# mrShark_05_a.net
KiCad netlist of a schematic drawn in EAGLE
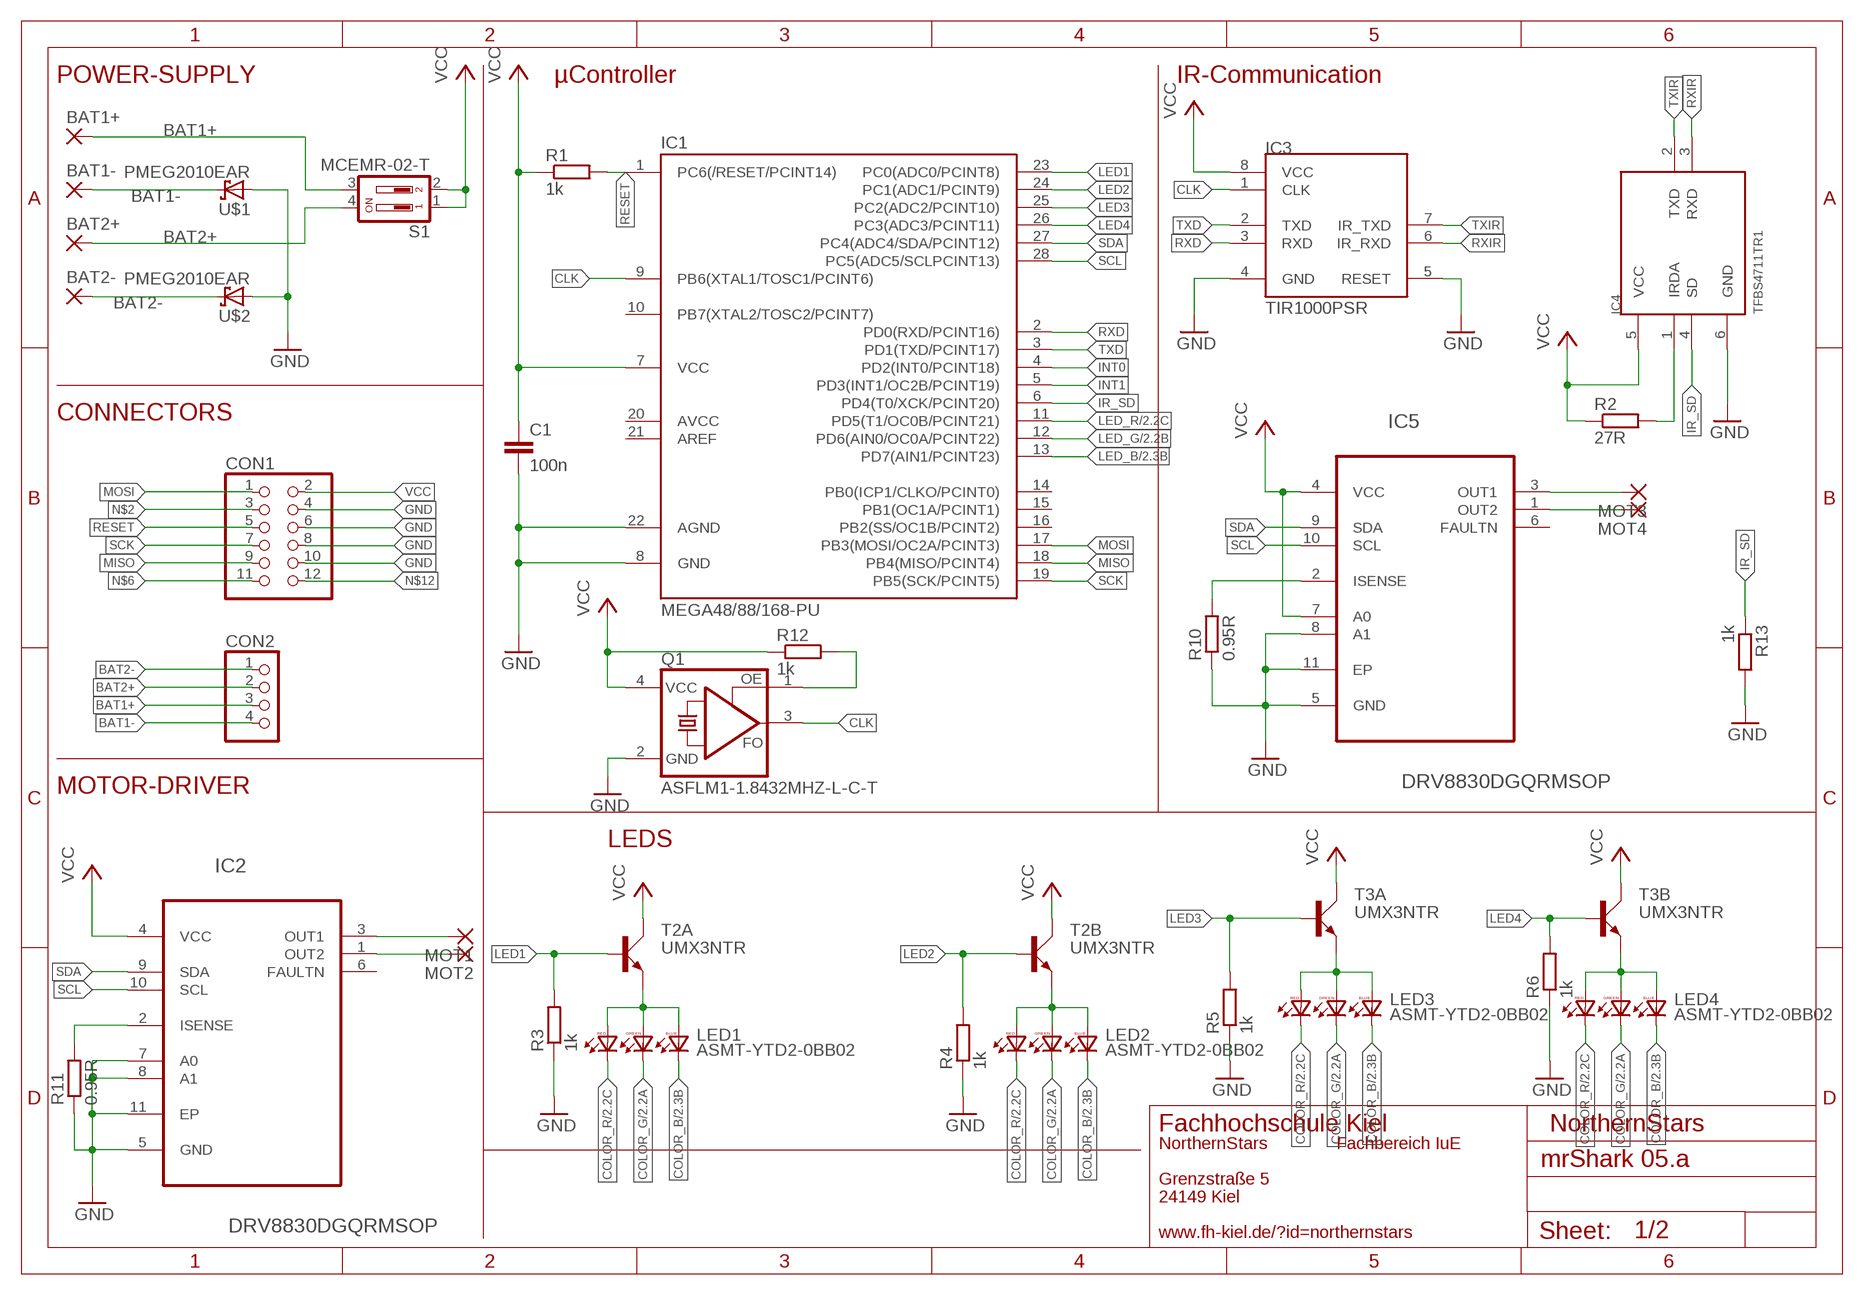
[diagram p0: schematic, sheet 1]
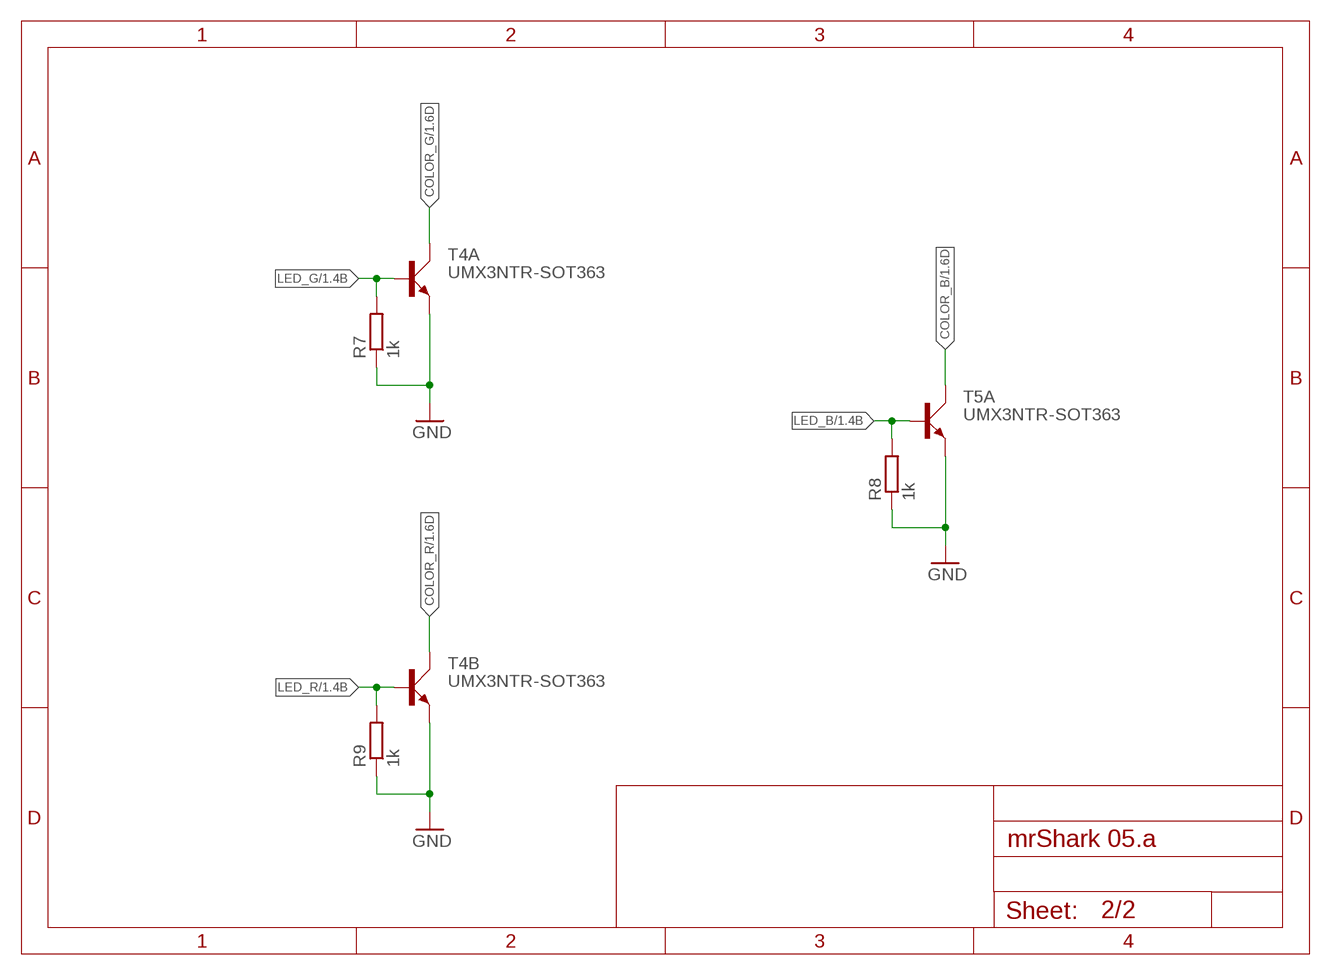
[diagram p1: schematic, sheet 2]

(export (version "E")
  (design (tool "Eeschema 10.0.6"))
  (components
    (comp (ref "R7")
      (value "1k")
      (footprint "eagle-import:R1206")
      (libsource (lib "eagle-import") (part "R-EU_R1206"))
    )
    (comp (ref "R8")
      (value "1k")
      (footprint "eagle-import:R1206")
      (libsource (lib "eagle-import") (part "R-EU_R1206"))
    )
    (comp (ref "R9")
      (value "1k")
      (footprint "eagle-import:R1206")
      (libsource (lib "eagle-import") (part "R-EU_R1206"))
    )
    (comp (ref "T4")
      (value "UMX3NTR-SOT363")
      (footprint "eagle-import:SOT363_INFINEON")
      (libsource (lib "eagle-import") (part "UMX3NTR-SOT363"))
    )
    (comp (ref "T5")
      (value "UMX3NTR-SOT363")
      (footprint "eagle-import:SOT363_INFINEON")
      (libsource (lib "eagle-import") (part "UMX3NTR-SOT363"))
    )
    (comp (ref "BAT1+")
      (value "1,6/0,9")
      (footprint "eagle-import:1,6_0,9")
      (libsource (lib "eagle-import") (part "1,6/0,9"))
    )
    (comp (ref "BAT1-")
      (value "1,6/0,9")
      (footprint "eagle-import:1,6_0,9")
      (libsource (lib "eagle-import") (part "1,6/0,9"))
    )
    (comp (ref "BAT2+")
      (value "1,6/0,9")
      (footprint "eagle-import:1,6_0,9")
      (libsource (lib "eagle-import") (part "1,6/0,9"))
    )
    (comp (ref "BAT2-")
      (value "1,6/0,9")
      (footprint "eagle-import:1,6_0,9")
      (libsource (lib "eagle-import") (part "1,6/0,9"))
    )
    (comp (ref "C1")
      (value "100n")
      (footprint "eagle-import:C1206")
      (libsource (lib "eagle-import") (part "C-EUC1206"))
    )
    (comp (ref "CON1")
      (value "PINHD-2X06_2.54-SMD")
      (footprint "eagle-import:2X06SMD")
      (libsource (lib "eagle-import") (part "PINHD-2X06_2.54-SMD"))
    )
    (comp (ref "CON2")
      (value "PINHD-1X04_2.54-SMD-90°")
      (footprint "eagle-import:1X04SMD_90")
      (libsource (lib "eagle-import") (part "PINHD-1X04_2.54-SMD-90°"))
    )
    (comp (ref "IC1")
      (value "MEGA48/88/168-PU")
      (footprint "eagle-import:DIL28-3")
      (libsource (lib "eagle-import") (part "MEGA48/88/168-PU"))
    )
    (comp (ref "IC2")
      (value "DRV8830DGQRMSOP")
      (footprint "eagle-import:SOP65P640X110-15N")
      (fields (field (name "MPN") "DRV8830DGQR"))
      (libsource (lib "eagle-import") (part "DRV8830DGQRMSOP"))
    )
    (comp (ref "IC3")
      (value "TIR1000PSR")
      (footprint "eagle-import:SO-08")
      (libsource (lib "eagle-import") (part "TIR1000PSR"))
    )
    (comp (ref "IC4")
      (value "TFBS4711TR1")
      (footprint "eagle-import:TFBS4711")
      (libsource (lib "eagle-import") (part "TFBS4711TR1"))
    )
    (comp (ref "IC5")
      (value "DRV8830DGQRMSOP")
      (footprint "eagle-import:SOP65P640X110-15N")
      (fields (field (name "MPN") "DRV8830DGQR"))
      (libsource (lib "eagle-import") (part "DRV8830DGQRMSOP"))
    )
    (comp (ref "LED1")
      (value "ASMT-YTD2-0BB02")
      (footprint "eagle-import:PLCC6")
      (libsource (lib "eagle-import") (part "PLCC6"))
    )
    (comp (ref "LED2")
      (value "ASMT-YTD2-0BB02")
      (footprint "eagle-import:PLCC6")
      (libsource (lib "eagle-import") (part "PLCC6"))
    )
    (comp (ref "LED3")
      (value "ASMT-YTD2-0BB02")
      (footprint "eagle-import:PLCC6")
      (libsource (lib "eagle-import") (part "PLCC6"))
    )
    (comp (ref "LED4")
      (value "ASMT-YTD2-0BB02")
      (footprint "eagle-import:PLCC6")
      (libsource (lib "eagle-import") (part "PLCC6"))
    )
    (comp (ref "MOT1")
      (value "1,6/0,9")
      (footprint "eagle-import:1,6_0,9")
      (libsource (lib "eagle-import") (part "1,6/0,9"))
    )
    (comp (ref "MOT2")
      (value "1,6/0,9")
      (footprint "eagle-import:1,6_0,9")
      (libsource (lib "eagle-import") (part "1,6/0,9"))
    )
    (comp (ref "MOT3")
      (value "1,6/0,9")
      (footprint "eagle-import:1,6_0,9")
      (libsource (lib "eagle-import") (part "1,6/0,9"))
    )
    (comp (ref "MOT4")
      (value "1,6/0,9")
      (footprint "eagle-import:1,6_0,9")
      (libsource (lib "eagle-import") (part "1,6/0,9"))
    )
    (comp (ref "Q1")
      (value "ASFLM1-1.8432MHZ-L-C-T")
      (footprint "eagle-import:HC536")
      (libsource (lib "eagle-import") (part "HC536R"))
    )
    (comp (ref "R1")
      (value "1k")
      (footprint "eagle-import:R1206")
      (libsource (lib "eagle-import") (part "R-EU_R1206"))
    )
    (comp (ref "R2")
      (value "27R")
      (footprint "eagle-import:R1206")
      (libsource (lib "eagle-import") (part "R-EU_R1206"))
    )
    (comp (ref "R3")
      (value "1k")
      (footprint "eagle-import:R1206")
      (libsource (lib "eagle-import") (part "R-EU_R1206"))
    )
    (comp (ref "R4")
      (value "1k")
      (footprint "eagle-import:R1206")
      (libsource (lib "eagle-import") (part "R-EU_R1206"))
    )
    (comp (ref "R5")
      (value "1k")
      (footprint "eagle-import:R1206")
      (libsource (lib "eagle-import") (part "R-EU_R1206"))
    )
    (comp (ref "R6")
      (value "1k")
      (footprint "eagle-import:R1206")
      (libsource (lib "eagle-import") (part "R-EU_R1206"))
    )
    (comp (ref "R10")
      (value "0.95R")
      (footprint "eagle-import:R1206")
      (libsource (lib "eagle-import") (part "R-EU_R1206"))
    )
    (comp (ref "R11")
      (value "0.95R")
      (footprint "eagle-import:R1206")
      (libsource (lib "eagle-import") (part "R-EU_R1206"))
    )
    (comp (ref "R12")
      (value "1k")
      (footprint "eagle-import:R1206")
      (libsource (lib "eagle-import") (part "R-EU_R1206"))
    )
    (comp (ref "R13")
      (value "1k")
      (footprint "eagle-import:R1206")
      (libsource (lib "eagle-import") (part "R-EU_R1206"))
    )
    (comp (ref "S1")
      (value "MCEMR-02-T")
      (footprint "eagle-import:CTS-219-02")
      (libsource (lib "eagle-import") (part "219-02"))
    )
    (comp (ref "T2")
      (value "UMX3NTR")
      (footprint "eagle-import:SOT363_INFINEON")
      (libsource (lib "eagle-import") (part "UMX3NTR-SOT363"))
    )
    (comp (ref "T3")
      (value "UMX3NTR")
      (footprint "eagle-import:SOT363_INFINEON")
      (libsource (lib "eagle-import") (part "UMX3NTR-SOT363"))
    )
    (comp (ref "U$1")
      (value "PMEG2010EAR")
      (footprint "eagle-import:SOD323-R")
      (libsource (lib "eagle-import") (part "PMEG2010EAR"))
    )
    (comp (ref "U$2")
      (value "PMEG2010EAR")
      (footprint "eagle-import:SOD323-R")
      (libsource (lib "eagle-import") (part "PMEG2010EAR"))
    )
  )
  (nets
    (net (code "1") (name "BAT1+") (class "Default")
      (node (ref "BAT1+") (pin "1") (pinfunction "P_1") (pintype "passive"))
      (node (ref "CON2") (pin "3") (pinfunction "3_3") (pintype "passive"))
      (node (ref "S1") (pin "3") (pinfunction "3_3") (pintype "passive"))
    )
    (net (code "2") (name "BAT1-") (class "Default")
      (node (ref "BAT1-") (pin "1") (pinfunction "P_1") (pintype "passive"))
      (node (ref "CON2") (pin "4") (pinfunction "4_4") (pintype "passive"))
      (node (ref "U$1") (pin "C") (pinfunction "C_C") (pintype "passive"))
    )
    (net (code "3") (name "BAT2+") (class "Default")
      (node (ref "BAT2+") (pin "1") (pinfunction "P_1") (pintype "passive"))
      (node (ref "CON2") (pin "2") (pinfunction "2_2") (pintype "passive"))
      (node (ref "S1") (pin "4") (pinfunction "4_4") (pintype "passive"))
    )
    (net (code "4") (name "BAT2-") (class "Default")
      (node (ref "BAT2-") (pin "1") (pinfunction "P_1") (pintype "passive"))
      (node (ref "CON2") (pin "1") (pinfunction "1_1") (pintype "passive"))
      (node (ref "U$2") (pin "C") (pinfunction "C_C") (pintype "passive"))
    )
    (net (code "5") (name "CLK") (class "Default")
      (node (ref "IC1") (pin "9") (pinfunction "PB6(XTAL1/TOSC1/PCINT6)_9") (pintype "bidirectional"))
      (node (ref "IC3") (pin "1") (pinfunction "CLK_1") (pintype "bidirectional"))
      (node (ref "Q1") (pin "3") (pinfunction "FO_3") (pintype "output"))
    )
    (net (code "6") (name "COLOR_B") (class "Default")
      (node (ref "LED1") (pin "1") (pinfunction "BC_1") (pintype "passive"))
      (node (ref "LED2") (pin "1") (pinfunction "BC_1") (pintype "passive"))
      (node (ref "LED3") (pin "1") (pinfunction "BC_1") (pintype "passive"))
      (node (ref "LED4") (pin "1") (pinfunction "BC_1") (pintype "passive"))
      (node (ref "T5") (pin "6") (pinfunction "C_6") (pintype "passive"))
    )
    (net (code "7") (name "COLOR_G") (class "Default")
      (node (ref "LED1") (pin "2") (pinfunction "GC_2") (pintype "passive"))
      (node (ref "LED2") (pin "2") (pinfunction "GC_2") (pintype "passive"))
      (node (ref "LED3") (pin "2") (pinfunction "GC_2") (pintype "passive"))
      (node (ref "LED4") (pin "2") (pinfunction "GC_2") (pintype "passive"))
      (node (ref "T4") (pin "6") (pinfunction "C_6") (pintype "passive"))
    )
    (net (code "8") (name "COLOR_R") (class "Default")
      (node (ref "LED1") (pin "3") (pinfunction "RC_3") (pintype "passive"))
      (node (ref "LED2") (pin "3") (pinfunction "RC_3") (pintype "passive"))
      (node (ref "LED3") (pin "3") (pinfunction "RC_3") (pintype "passive"))
      (node (ref "LED4") (pin "3") (pinfunction "RC_3") (pintype "passive"))
      (node (ref "T4") (pin "4") (pinfunction "C_4") (pintype "passive"))
    )
    (net (code "9") (name "GND") (class "Default")
      (node (ref "C1") (pin "2") (pinfunction "2_2") (pintype "passive"))
      (node (ref "CON1") (pin "10") (pinfunction "10_10") (pintype "passive"))
      (node (ref "CON1") (pin "4") (pinfunction "4_4") (pintype "passive"))
      (node (ref "CON1") (pin "6") (pinfunction "6_6") (pintype "passive"))
      (node (ref "CON1") (pin "8") (pinfunction "8_8") (pintype "passive"))
      (node (ref "IC1") (pin "22") (pinfunction "AGND_22") (pintype "power_in"))
      (node (ref "IC1") (pin "8") (pinfunction "GND_8") (pintype "power_in"))
      (node (ref "IC2") (pin "11") (pinfunction "EP_11") (pintype "passive"))
      (node (ref "IC2") (pin "5") (pinfunction "GND_5") (pintype "passive"))
      (node (ref "IC2") (pin "7") (pinfunction "A0_7") (pintype "input"))
      (node (ref "IC2") (pin "8") (pinfunction "A1_8") (pintype "input"))
      (node (ref "IC3") (pin "4") (pinfunction "GND_4") (pintype "bidirectional"))
      (node (ref "IC3") (pin "5") (pinfunction "RESET_5") (pintype "bidirectional"))
      (node (ref "IC4") (pin "6") (pinfunction "GND_6") (pintype "bidirectional"))
      (node (ref "IC5") (pin "11") (pinfunction "EP_11") (pintype "passive"))
      (node (ref "IC5") (pin "5") (pinfunction "GND_5") (pintype "passive"))
      (node (ref "IC5") (pin "8") (pinfunction "A1_8") (pintype "input"))
      (node (ref "Q1") (pin "2") (pinfunction "GND_2") (pintype "power_in"))
      (node (ref "R10") (pin "1") (pinfunction "1_1") (pintype "passive"))
      (node (ref "R11") (pin "1") (pinfunction "1_1") (pintype "passive"))
      (node (ref "R13") (pin "2") (pinfunction "2_2") (pintype "passive"))
      (node (ref "R3") (pin "1") (pinfunction "1_1") (pintype "passive"))
      (node (ref "R4") (pin "1") (pinfunction "1_1") (pintype "passive"))
      (node (ref "R5") (pin "1") (pinfunction "1_1") (pintype "passive"))
      (node (ref "R6") (pin "1") (pinfunction "1_1") (pintype "passive"))
      (node (ref "R7") (pin "1") (pinfunction "1_1") (pintype "passive"))
      (node (ref "R8") (pin "1") (pinfunction "1_1") (pintype "passive"))
      (node (ref "R9") (pin "1") (pinfunction "1_1") (pintype "passive"))
      (node (ref "T4") (pin "1") (pinfunction "E_1") (pintype "passive"))
      (node (ref "T4") (pin "5") (pinfunction "E_5") (pintype "passive"))
      (node (ref "T5") (pin "1") (pinfunction "E_1") (pintype "passive"))
      (node (ref "U$1") (pin "A") (pinfunction "A_A") (pintype "passive"))
      (node (ref "U$2") (pin "A") (pinfunction "A_A") (pintype "passive"))
    )
    (net (code "10") (name "INT0") (class "Default")
      (node (ref "IC1") (pin "4") (pinfunction "PD2(INT0/PCINT18)_4") (pintype "bidirectional"))
    )
    (net (code "11") (name "INT1") (class "Default")
      (node (ref "IC1") (pin "5") (pinfunction "PD3(INT1/OC2B/PCINT19)_5") (pintype "bidirectional"))
    )
    (net (code "12") (name "IR_SD") (class "Default")
      (node (ref "IC1") (pin "6") (pinfunction "PD4(T0/XCK/PCINT20)_6") (pintype "bidirectional"))
      (node (ref "IC4") (pin "4") (pinfunction "SD_4") (pintype "bidirectional"))
      (node (ref "R13") (pin "1") (pinfunction "1_1") (pintype "passive"))
    )
    (net (code "13") (name "LED1") (class "Default")
      (node (ref "IC1") (pin "23") (pinfunction "PC0(ADC0/PCINT8)_23") (pintype "bidirectional"))
      (node (ref "R3") (pin "2") (pinfunction "2_2") (pintype "passive"))
      (node (ref "T2") (pin "2") (pinfunction "B_2") (pintype "passive"))
    )
    (net (code "14") (name "LED2") (class "Default")
      (node (ref "IC1") (pin "24") (pinfunction "PC1(ADC1/PCINT9)_24") (pintype "bidirectional"))
      (node (ref "R4") (pin "2") (pinfunction "2_2") (pintype "passive"))
      (node (ref "T2") (pin "3") (pinfunction "B_3") (pintype "passive"))
    )
    (net (code "15") (name "LED3") (class "Default")
      (node (ref "IC1") (pin "25") (pinfunction "PC2(ADC2/PCINT10)_25") (pintype "bidirectional"))
      (node (ref "R5") (pin "2") (pinfunction "2_2") (pintype "passive"))
      (node (ref "T3") (pin "2") (pinfunction "B_2") (pintype "passive"))
    )
    (net (code "16") (name "LED4") (class "Default")
      (node (ref "IC1") (pin "26") (pinfunction "PC3(ADC3/PCINT11)_26") (pintype "bidirectional"))
      (node (ref "R6") (pin "2") (pinfunction "2_2") (pintype "passive"))
      (node (ref "T3") (pin "3") (pinfunction "B_3") (pintype "passive"))
    )
    (net (code "17") (name "LED_B") (class "Default")
      (node (ref "IC1") (pin "13") (pinfunction "PD7(AIN1/PCINT23)_13") (pintype "bidirectional"))
      (node (ref "R8") (pin "2") (pinfunction "2_2") (pintype "passive"))
      (node (ref "T5") (pin "2") (pinfunction "B_2") (pintype "passive"))
    )
    (net (code "18") (name "LED_G") (class "Default")
      (node (ref "IC1") (pin "12") (pinfunction "PD6(AIN0/OC0A/PCINT22)_12") (pintype "bidirectional"))
      (node (ref "R7") (pin "2") (pinfunction "2_2") (pintype "passive"))
      (node (ref "T4") (pin "2") (pinfunction "B_2") (pintype "passive"))
    )
    (net (code "19") (name "LED_R") (class "Default")
      (node (ref "IC1") (pin "11") (pinfunction "PD5(T1/OC0B/PCINT21)_11") (pintype "bidirectional"))
      (node (ref "R9") (pin "2") (pinfunction "2_2") (pintype "passive"))
      (node (ref "T4") (pin "3") (pinfunction "B_3") (pintype "passive"))
    )
    (net (code "20") (name "MISO") (class "Default")
      (node (ref "CON1") (pin "9") (pinfunction "9_9") (pintype "passive"))
      (node (ref "IC1") (pin "18") (pinfunction "PB4(MISO/PCINT4)_18") (pintype "bidirectional"))
    )
    (net (code "21") (name "MOSI") (class "Default")
      (node (ref "CON1") (pin "1") (pinfunction "1_1") (pintype "passive"))
      (node (ref "IC1") (pin "17") (pinfunction "PB3(MOSI/OC2A/PCINT3)_17") (pintype "bidirectional"))
    )
    (net (code "22") (name "N$2") (class "Default")
      (node (ref "CON1") (pin "3") (pinfunction "3_3") (pintype "passive"))
    )
    (net (code "23") (name "N$6") (class "Default")
      (node (ref "CON1") (pin "11") (pinfunction "11_11") (pintype "passive"))
    )
    (net (code "24") (name "N$12") (class "Default")
      (node (ref "CON1") (pin "12") (pinfunction "12_12") (pintype "passive"))
    )
    (net (code "25") (name "Net-(IC2-ISENSE)") (class "Default")
      (node (ref "IC2") (pin "2") (pinfunction "ISENSE_2") (pintype "input"))
      (node (ref "R11") (pin "2") (pinfunction "2_2") (pintype "passive"))
    )
    (net (code "26") (name "Net-(IC2-OUT1)") (class "Default")
      (node (ref "IC2") (pin "3") (pinfunction "OUT1_3") (pintype "output"))
      (node (ref "MOT1") (pin "1") (pinfunction "P_1") (pintype "passive"))
    )
    (net (code "27") (name "Net-(IC2-OUT2)") (class "Default")
      (node (ref "IC2") (pin "1") (pinfunction "OUT2_1") (pintype "output"))
      (node (ref "MOT2") (pin "1") (pinfunction "P_1") (pintype "passive"))
    )
    (net (code "28") (name "Net-(IC4-IRDA)") (class "Default")
      (node (ref "IC4") (pin "1") (pinfunction "IRDA_1") (pintype "bidirectional"))
      (node (ref "R2") (pin "2") (pinfunction "2_2") (pintype "passive"))
    )
    (net (code "29") (name "Net-(IC5-ISENSE)") (class "Default")
      (node (ref "IC5") (pin "2") (pinfunction "ISENSE_2") (pintype "input"))
      (node (ref "R10") (pin "2") (pinfunction "2_2") (pintype "passive"))
    )
    (net (code "30") (name "Net-(IC5-OUT1)") (class "Default")
      (node (ref "IC5") (pin "3") (pinfunction "OUT1_3") (pintype "output"))
      (node (ref "MOT3") (pin "1") (pinfunction "P_1") (pintype "passive"))
    )
    (net (code "31") (name "Net-(IC5-OUT2)") (class "Default")
      (node (ref "IC5") (pin "1") (pinfunction "OUT2_1") (pintype "output"))
      (node (ref "MOT4") (pin "1") (pinfunction "P_1") (pintype "passive"))
    )
    (net (code "32") (name "Net-(LED1-BA)") (class "Default")
      (node (ref "LED1") (pin "4") (pinfunction "RA_4") (pintype "passive"))
      (node (ref "LED1") (pin "5") (pinfunction "GA_5") (pintype "passive"))
      (node (ref "LED1") (pin "6") (pinfunction "BA_6") (pintype "passive"))
      (node (ref "T2") (pin "1") (pinfunction "E_1") (pintype "passive"))
    )
    (net (code "33") (name "Net-(LED2-BA)") (class "Default")
      (node (ref "LED2") (pin "4") (pinfunction "RA_4") (pintype "passive"))
      (node (ref "LED2") (pin "5") (pinfunction "GA_5") (pintype "passive"))
      (node (ref "LED2") (pin "6") (pinfunction "BA_6") (pintype "passive"))
      (node (ref "T2") (pin "5") (pinfunction "E_5") (pintype "passive"))
    )
    (net (code "34") (name "Net-(LED3-BA)") (class "Default")
      (node (ref "LED3") (pin "4") (pinfunction "RA_4") (pintype "passive"))
      (node (ref "LED3") (pin "5") (pinfunction "GA_5") (pintype "passive"))
      (node (ref "LED3") (pin "6") (pinfunction "BA_6") (pintype "passive"))
      (node (ref "T3") (pin "1") (pinfunction "E_1") (pintype "passive"))
    )
    (net (code "35") (name "Net-(LED4-BA)") (class "Default")
      (node (ref "LED4") (pin "4") (pinfunction "RA_4") (pintype "passive"))
      (node (ref "LED4") (pin "5") (pinfunction "GA_5") (pintype "passive"))
      (node (ref "LED4") (pin "6") (pinfunction "BA_6") (pintype "passive"))
      (node (ref "T3") (pin "5") (pinfunction "E_5") (pintype "passive"))
    )
    (net (code "36") (name "Net-(Q1-OE)") (class "Default")
      (node (ref "Q1") (pin "1") (pinfunction "OE_1") (pintype "input"))
      (node (ref "R12") (pin "2") (pinfunction "2_2") (pintype "passive"))
    )
    (net (code "37") (name "RESET") (class "Default")
      (node (ref "CON1") (pin "5") (pinfunction "5_5") (pintype "passive"))
      (node (ref "IC1") (pin "1") (pinfunction "PC6(/RESET/PCINT14)_1") (pintype "bidirectional"))
      (node (ref "R1") (pin "2") (pinfunction "2_2") (pintype "passive"))
    )
    (net (code "38") (name "RXD") (class "Default")
      (node (ref "IC1") (pin "2") (pinfunction "PD0(RXD/PCINT16)_2") (pintype "bidirectional"))
      (node (ref "IC3") (pin "3") (pinfunction "RXD_3") (pintype "bidirectional"))
    )
    (net (code "39") (name "RXIR") (class "Default")
      (node (ref "IC3") (pin "6") (pinfunction "IR_RXD_6") (pintype "bidirectional"))
      (node (ref "IC4") (pin "3") (pinfunction "RXD_3") (pintype "output"))
    )
    (net (code "40") (name "SCK") (class "Default")
      (node (ref "CON1") (pin "7") (pinfunction "7_7") (pintype "passive"))
      (node (ref "IC1") (pin "19") (pinfunction "PB5(SCK/PCINT5)_19") (pintype "bidirectional"))
    )
    (net (code "41") (name "SCL") (class "Default")
      (node (ref "IC1") (pin "28") (pinfunction "PC5(ADC5/SCLPCINT13)_28") (pintype "bidirectional"))
      (node (ref "IC2") (pin "10") (pinfunction "SCL_10") (pintype "input"))
      (node (ref "IC5") (pin "10") (pinfunction "SCL_10") (pintype "input"))
    )
    (net (code "42") (name "SDA") (class "Default")
      (node (ref "IC1") (pin "27") (pinfunction "PC4(ADC4/SDA/PCINT12)_27") (pintype "bidirectional"))
      (node (ref "IC2") (pin "9") (pinfunction "SDA_9") (pintype "bidirectional"))
      (node (ref "IC5") (pin "9") (pinfunction "SDA_9") (pintype "bidirectional"))
    )
    (net (code "43") (name "TXD") (class "Default")
      (node (ref "IC1") (pin "3") (pinfunction "PD1(TXD/PCINT17)_3") (pintype "bidirectional"))
      (node (ref "IC3") (pin "2") (pinfunction "TXD_2") (pintype "bidirectional"))
    )
    (net (code "44") (name "TXIR") (class "Default")
      (node (ref "IC3") (pin "7") (pinfunction "IR_TXD_7") (pintype "bidirectional"))
      (node (ref "IC4") (pin "2") (pinfunction "TXD_2") (pintype "input"))
    )
    (net (code "45") (name "VCC") (class "Default")
      (node (ref "C1") (pin "1") (pinfunction "1_1") (pintype "passive"))
      (node (ref "CON1") (pin "2") (pinfunction "2_2") (pintype "passive"))
      (node (ref "IC1") (pin "7") (pinfunction "VCC_7") (pintype "power_in"))
      (node (ref "IC2") (pin "4") (pinfunction "VCC_4") (pintype "power_in"))
      (node (ref "IC3") (pin "8") (pinfunction "VCC_8") (pintype "bidirectional"))
      (node (ref "IC4") (pin "5") (pinfunction "VCC_5") (pintype "power_in"))
      (node (ref "IC5") (pin "4") (pinfunction "VCC_4") (pintype "power_in"))
      (node (ref "IC5") (pin "7") (pinfunction "A0_7") (pintype "input"))
      (node (ref "Q1") (pin "4") (pinfunction "VCC_4") (pintype "power_in"))
      (node (ref "R1") (pin "1") (pinfunction "1_1") (pintype "passive"))
      (node (ref "R12") (pin "1") (pinfunction "1_1") (pintype "passive"))
      (node (ref "R2") (pin "1") (pinfunction "1_1") (pintype "passive"))
      (node (ref "S1") (pin "1") (pinfunction "1_1") (pintype "passive"))
      (node (ref "S1") (pin "2") (pinfunction "2_2") (pintype "passive"))
      (node (ref "T2") (pin "4") (pinfunction "C_4") (pintype "passive"))
      (node (ref "T2") (pin "6") (pinfunction "C_6") (pintype "passive"))
      (node (ref "T3") (pin "4") (pinfunction "C_4") (pintype "passive"))
      (node (ref "T3") (pin "6") (pinfunction "C_6") (pintype "passive"))
    )
    (net (code "46") (name "unconnected-(IC1-AREF-Pad21)") (class "Default")
      (node (ref "IC1") (pin "21") (pinfunction "AREF_21") (pintype "passive"))
    )
    (net (code "47") (name "unconnected-(IC1-AVCC-Pad20)") (class "Default")
      (node (ref "IC1") (pin "20") (pinfunction "AVCC_20") (pintype "passive"))
    )
    (net (code "48") (name "unconnected-(IC1-PB0(ICP1{slash}CLKO{slash}PCINT0)-Pad14)") (class "Default")
      (node (ref "IC1") (pin "14") (pinfunction "PB0(ICP1/CLKO/PCINT0)_14") (pintype "bidirectional"))
    )
    (net (code "49") (name "unconnected-(IC1-PB1(OC1A{slash}PCINT1)-Pad15)") (class "Default")
      (node (ref "IC1") (pin "15") (pinfunction "PB1(OC1A/PCINT1)_15") (pintype "bidirectional"))
    )
    (net (code "50") (name "unconnected-(IC1-PB2(SS{slash}OC1B{slash}PCINT2)-Pad16)") (class "Default")
      (node (ref "IC1") (pin "16") (pinfunction "PB2(SS/OC1B/PCINT2)_16") (pintype "bidirectional"))
    )
    (net (code "51") (name "unconnected-(IC1-PB7(XTAL2{slash}TOSC2{slash}PCINT7)-Pad10)") (class "Default")
      (node (ref "IC1") (pin "10") (pinfunction "PB7(XTAL2/TOSC2/PCINT7)_10") (pintype "bidirectional"))
    )
    (net (code "52") (name "unconnected-(IC2-FAULTN-Pad6)") (class "Default")
      (node (ref "IC2") (pin "6") (pinfunction "FAULTN_6") (pintype "output"))
    )
    (net (code "53") (name "unconnected-(IC5-FAULTN-Pad6)") (class "Default")
      (node (ref "IC5") (pin "6") (pinfunction "FAULTN_6") (pintype "output"))
    )
  )
)
